# Socket.net
KiCad netlist of a schematic drawn in Altium Designer
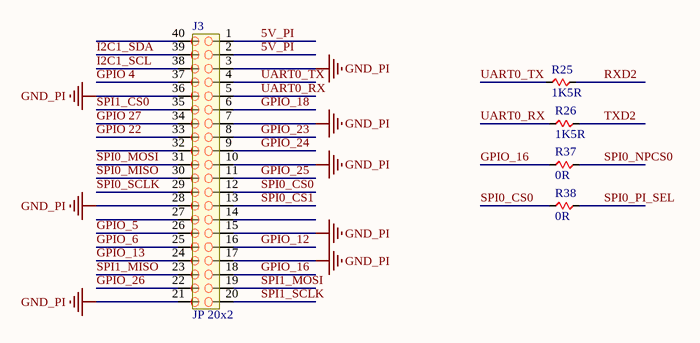
[diagram p0: Socket.SchDoc]

(export (version "E")
  (design (tool "Eeschema 10.0.6"))
  (components
    (comp (ref "J3") (value "JP 20x2") (footprint "JP 20x2") (libsource (lib "SkyWar") (part "JP 20x2")))
    (comp (ref "R25") (value "1K5R") (footprint "R 0805") (libsource (lib "SkyWar") (part "R 0805")))
    (comp (ref "R26") (value "1K5R") (footprint "R 0805") (libsource (lib "SkyWar") (part "R 0805")))
    (comp (ref "R37") (value "0R") (footprint "R 0805") (libsource (lib "SkyWar") (part "R 0805")))
    (comp (ref "R38") (value "0R") (footprint "R 0805") (libsource (lib "SkyWar") (part "R 0805")))
  )
  (nets
    (net (code "1") (name "/5V_PI") (class "Default")
      (node (ref "J3") (pin "1") (pinfunction "6_1") (pintype "passive"))
      (node (ref "J3") (pin "2") (pinfunction "7_2") (pintype "passive"))
    )
    (net (code "2") (name "/GPIO 4") (class "Default")
      (node (ref "J3") (pin "37") (pinfunction "42_37") (pintype "passive"))
    )
    (net (code "3") (name "/GPIO 22") (class "Default")
      (node (ref "J3") (pin "33") (pinfunction "38_33") (pintype "passive"))
    )
    (net (code "4") (name "/GPIO 27") (class "Default")
      (node (ref "J3") (pin "34") (pinfunction "39_34") (pintype "passive"))
    )
    (net (code "5") (name "/GPIO_5") (class "Default")
      (node (ref "J3") (pin "26") (pinfunction "31_26") (pintype "passive"))
    )
    (net (code "6") (name "/GPIO_6") (class "Default")
      (node (ref "J3") (pin "25") (pinfunction "30_25") (pintype "passive"))
    )
    (net (code "7") (name "/GPIO_12") (class "Default")
      (node (ref "J3") (pin "16") (pinfunction "21_16") (pintype "passive"))
    )
    (net (code "8") (name "/GPIO_13") (class "Default")
      (node (ref "J3") (pin "24") (pinfunction "29_24") (pintype "passive"))
    )
    (net (code "9") (name "/GPIO_16") (class "Default")
      (node (ref "J3") (pin "18") (pinfunction "23_18") (pintype "passive"))
      (node (ref "R37") (pin "1") (pinfunction "0_1") (pintype "passive"))
    )
    (net (code "10") (name "/GPIO_18") (class "Default")
      (node (ref "J3") (pin "6") (pinfunction "11_6") (pintype "passive"))
    )
    (net (code "11") (name "/GPIO_23") (class "Default")
      (node (ref "J3") (pin "8") (pinfunction "13_8") (pintype "passive"))
    )
    (net (code "12") (name "/GPIO_24") (class "Default")
      (node (ref "J3") (pin "9") (pinfunction "14_9") (pintype "passive"))
    )
    (net (code "13") (name "/GPIO_25") (class "Default")
      (node (ref "J3") (pin "11") (pinfunction "16_11") (pintype "passive"))
    )
    (net (code "14") (name "/GPIO_26") (class "Default")
      (node (ref "J3") (pin "22") (pinfunction "27_22") (pintype "passive"))
    )
    (net (code "15") (name "/I2C1_SCL") (class "Default")
      (node (ref "J3") (pin "38") (pinfunction "43_38") (pintype "passive"))
    )
    (net (code "16") (name "/I2C1_SDA") (class "Default")
      (node (ref "J3") (pin "39") (pinfunction "44_39") (pintype "passive"))
    )
    (net (code "17") (name "/RXD2") (class "Default")
      (node (ref "R25") (pin "2") (pinfunction "1_2") (pintype "passive"))
    )
    (net (code "18") (name "/SPI0_CS0") (class "Default")
      (node (ref "J3") (pin "12") (pinfunction "17_12") (pintype "passive"))
      (node (ref "R38") (pin "1") (pinfunction "0_1") (pintype "passive"))
    )
    (net (code "19") (name "/SPI0_CS1") (class "Default")
      (node (ref "J3") (pin "13") (pinfunction "18_13") (pintype "passive"))
    )
    (net (code "20") (name "/SPI0_MISO") (class "Default")
      (node (ref "J3") (pin "30") (pinfunction "35_30") (pintype "passive"))
    )
    (net (code "21") (name "/SPI0_MOSI") (class "Default")
      (node (ref "J3") (pin "31") (pinfunction "36_31") (pintype "passive"))
    )
    (net (code "22") (name "/SPI0_NPCS0") (class "Default")
      (node (ref "R37") (pin "2") (pinfunction "1_2") (pintype "passive"))
    )
    (net (code "23") (name "/SPI0_PI_SEL") (class "Default")
      (node (ref "R38") (pin "2") (pinfunction "1_2") (pintype "passive"))
    )
    (net (code "24") (name "/SPI0_SCLK") (class "Default")
      (node (ref "J3") (pin "29") (pinfunction "34_29") (pintype "passive"))
    )
    (net (code "25") (name "/SPI1_CS0") (class "Default")
      (node (ref "J3") (pin "35") (pinfunction "40_35") (pintype "passive"))
    )
    (net (code "26") (name "/SPI1_MISO") (class "Default")
      (node (ref "J3") (pin "23") (pinfunction "28_23") (pintype "passive"))
    )
    (net (code "27") (name "/SPI1_MOSI") (class "Default")
      (node (ref "J3") (pin "19") (pinfunction "24_19") (pintype "passive"))
    )
    (net (code "28") (name "/SPI1_SCLK") (class "Default")
      (node (ref "J3") (pin "20") (pinfunction "25_20") (pintype "passive"))
    )
    (net (code "29") (name "/TXD2") (class "Default")
      (node (ref "R26") (pin "2") (pinfunction "1_2") (pintype "passive"))
    )
    (net (code "30") (name "/UART0_RX") (class "Default")
      (node (ref "J3") (pin "5") (pinfunction "10_5") (pintype "passive"))
      (node (ref "R26") (pin "1") (pinfunction "0_1") (pintype "passive"))
    )
    (net (code "31") (name "/UART0_TX") (class "Default")
      (node (ref "J3") (pin "4") (pinfunction "9_4") (pintype "passive"))
      (node (ref "R25") (pin "1") (pinfunction "0_1") (pintype "passive"))
    )
    (net (code "32") (name "GND_PI") (class "Default")
      (node (ref "J3") (pin "10") (pinfunction "15_10") (pintype "passive"))
      (node (ref "J3") (pin "15") (pinfunction "20_15") (pintype "passive"))
      (node (ref "J3") (pin "17") (pinfunction "22_17") (pintype "passive"))
      (node (ref "J3") (pin "21") (pinfunction "26_21") (pintype "passive"))
      (node (ref "J3") (pin "28") (pinfunction "33_28") (pintype "passive"))
      (node (ref "J3") (pin "3") (pinfunction "8_3") (pintype "passive"))
      (node (ref "J3") (pin "36") (pinfunction "41_36") (pintype "passive"))
      (node (ref "J3") (pin "7") (pinfunction "12_7") (pintype "passive"))
    )
    (net (code "33") (name "unconnected-(J3-19-Pad14)") (class "Default")
      (node (ref "J3") (pin "14") (pinfunction "19_14") (pintype "passive"))
    )
    (net (code "34") (name "unconnected-(J3-32-Pad27)") (class "Default")
      (node (ref "J3") (pin "27") (pinfunction "32_27") (pintype "passive"))
    )
    (net (code "35") (name "unconnected-(J3-37-Pad32)") (class "Default")
      (node (ref "J3") (pin "32") (pinfunction "37_32") (pintype "passive"))
    )
    (net (code "36") (name "unconnected-(J3-45-Pad40)") (class "Default")
      (node (ref "J3") (pin "40") (pinfunction "45_40") (pintype "passive"))
    )
  )
)
